# Arlinked-Can.net
KiCad netlist of a schematic drawn in EAGLE
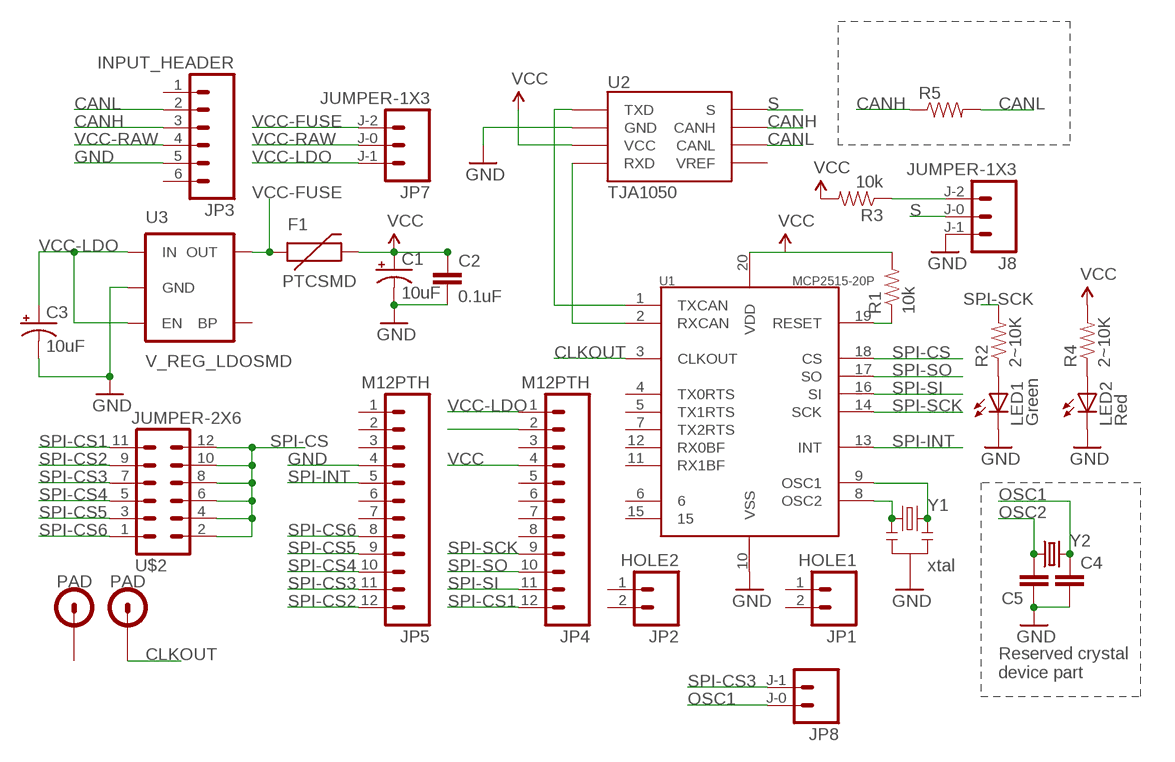
[diagram p0: schematic, sheet 1]

(export (version "E")
  (design (tool "Eeschema 10.0.6"))
  (components
    (comp (ref "C1")
      (value "10uF")
      (footprint "eagle-import:EIA3216")
      (libsource (lib "eagle-import") (part "CAP_POL1206"))
    )
    (comp (ref "C2")
      (value "0.1uF")
      (footprint "eagle-import:0402-CAP")
      (libsource (lib "eagle-import") (part "CAP0402-CAP"))
    )
    (comp (ref "C3")
      (value "10uF")
      (footprint "eagle-import:EIA3216")
      (libsource (lib "eagle-import") (part "CAP_POL1206"))
    )
    (comp (ref "C4")
      (value "CAP0402-CAP")
      (footprint "eagle-import:0402-CAP")
      (libsource (lib "eagle-import") (part "CAP0402-CAP"))
    )
    (comp (ref "C5")
      (value "CAP0402-CAP")
      (footprint "eagle-import:0402-CAP")
      (libsource (lib "eagle-import") (part "CAP0402-CAP"))
    )
    (comp (ref "F1")
      (value "PTCSMD")
      (footprint "eagle-import:PTC-1206")
      (libsource (lib "eagle-import") (part "PTCSMD"))
    )
    (comp (ref "J8")
      (value "JUMPER-1X3")
      (footprint "eagle-import:JUMPER-1X3-SMD-10")
      (libsource (lib "eagle-import") (part "JUMPER-1X3"))
    )
    (comp (ref "JP1")
      (value "HOLE1")
      (footprint "eagle-import:1X02")
      (libsource (lib "eagle-import") (part "M02PTH"))
    )
    (comp (ref "JP2")
      (value "HOLE2")
      (footprint "eagle-import:1X02")
      (libsource (lib "eagle-import") (part "M02PTH"))
    )
    (comp (ref "JP3")
      (value "INPUT_HEADER")
      (footprint "eagle-import:1X06")
      (libsource (lib "eagle-import") (part "M06SIP"))
    )
    (comp (ref "JP4")
      (value "M12PTH")
      (footprint "eagle-import:1X12")
      (libsource (lib "eagle-import") (part "M12PTH"))
    )
    (comp (ref "JP5")
      (value "M12PTH")
      (footprint "eagle-import:1X12")
      (libsource (lib "eagle-import") (part "M12PTH"))
    )
    (comp (ref "JP7")
      (value "JUMPER-1X3")
      (footprint "eagle-import:JUMPER-1X3-SMD-10")
      (libsource (lib "eagle-import") (part "JUMPER-1X3"))
    )
    (comp (ref "JP8")
      (value "JUMPER-1X2")
      (footprint "eagle-import:JUMPER-1X2-SMD-10")
      (libsource (lib "eagle-import") (part "JUMPER-1X2"))
    )
    (comp (ref "LED1")
      (value "Green")
      (footprint "eagle-import:LED-0603")
      (libsource (lib "eagle-import") (part "LED0603"))
    )
    (comp (ref "LED2")
      (value "Red")
      (footprint "eagle-import:LED-0603")
      (libsource (lib "eagle-import") (part "LED0603"))
    )
    (comp (ref "R1")
      (value "10k")
      (footprint "eagle-import:0603-RES")
      (libsource (lib "eagle-import") (part "RESISTOR0603-RES"))
    )
    (comp (ref "R2")
      (value "2~10K")
      (footprint "eagle-import:0402-RES")
      (libsource (lib "eagle-import") (part "RESISTOR0402-RES"))
    )
    (comp (ref "R3")
      (value "10k")
      (footprint "eagle-import:0603-RES")
      (libsource (lib "eagle-import") (part "RESISTOR0603-RES"))
    )
    (comp (ref "R4")
      (value "2~10K")
      (footprint "eagle-import:0402-RES")
      (libsource (lib "eagle-import") (part "RESISTOR0402-RES"))
    )
    (comp (ref "R5")
      (value "RESISTOR0603-RES")
      (footprint "eagle-import:0603-RES")
      (libsource (lib "eagle-import") (part "RESISTOR0603-RES"))
    )
    (comp (ref "U$1")
      (value "PAD")
      (footprint "eagle-import:PAD-HOLE-4MM")
      (libsource (lib "eagle-import") (part "PAD"))
    )
    (comp (ref "U$2")
      (value "JUMPER-2X6")
      (footprint "eagle-import:JUMPER-2X06-SMD")
      (libsource (lib "eagle-import") (part "JUMPER-2X6"))
    )
    (comp (ref "U$3")
      (value "PAD_SMD")
      (footprint "eagle-import:PAD-SMD-2MM")
      (libsource (lib "eagle-import") (part "PAD_SMD"))
    )
    (comp (ref "U1")
      (value "MCP2515-20P")
      (footprint "eagle-import:TSSOP20")
      (libsource (lib "eagle-import") (part "MCP2515-20P"))
    )
    (comp (ref "U2")
      (value "TJA1050")
      (footprint "eagle-import:SOIC-8")
      (libsource (lib "eagle-import") (part "TJA1050"))
    )
    (comp (ref "U3")
      (value "V_REG_LDOSMD")
      (footprint "eagle-import:SOT23-5")
      (libsource (lib "eagle-import") (part "V_REG_LDOSMD"))
    )
    (comp (ref "Y1")
      (value "xtal")
      (footprint "eagle-import:RESONATOR-SMD")
      (libsource (lib "eagle-import") (part "RESONATORSMD"))
    )
    (comp (ref "Y2")
      (value "CRYSTALPAD-ONLY")
      (footprint "eagle-import:HC49U-V")
      (libsource (lib "eagle-import") (part "CRYSTALPAD-ONLY"))
    )
  )
  (nets
    (net (code "1") (name "/CANH") (class "Default")
      (node (ref "JP3") (pin "3") (pinfunction "3_3") (pintype "passive"))
      (node (ref "R5") (pin "1") (pinfunction "1_1") (pintype "passive"))
      (node (ref "U2") (pin "7") (pinfunction "CANH_7") (pintype "bidirectional"))
    )
    (net (code "2") (name "/CANL") (class "Default")
      (node (ref "JP3") (pin "2") (pinfunction "2_2") (pintype "passive"))
      (node (ref "R5") (pin "2") (pinfunction "2_2") (pintype "passive"))
      (node (ref "U2") (pin "6") (pinfunction "CANL_6") (pintype "bidirectional"))
    )
    (net (code "3") (name "/CLKOUT") (class "Default")
      (node (ref "U$3") (pin "P$1") (pinfunction "P$1_P$1") (pintype "input"))
      (node (ref "U1") (pin "3") (pinfunction "CLKOUT_3") (pintype "bidirectional"))
    )
    (net (code "4") (name "/OSC1") (class "Default")
      (node (ref "C4") (pin "1") (pinfunction "1_1") (pintype "passive"))
      (node (ref "JP8") (pin "J-0") (pinfunction "J-1_J-0") (pintype "passive"))
      (node (ref "U1") (pin "9") (pinfunction "OSC1_9") (pintype "bidirectional"))
      (node (ref "Y1") (pin "3") (pinfunction "3_3") (pintype "passive"))
      (node (ref "Y2") (pin "2") (pinfunction "2_2") (pintype "passive"))
    )
    (net (code "5") (name "/OSC2") (class "Default")
      (node (ref "C5") (pin "2") (pinfunction "2_2") (pintype "passive"))
      (node (ref "U1") (pin "8") (pinfunction "OSC2_8") (pintype "bidirectional"))
      (node (ref "Y1") (pin "1") (pinfunction "1_1") (pintype "passive"))
      (node (ref "Y2") (pin "1") (pinfunction "1_1") (pintype "passive"))
    )
    (net (code "6") (name "/S") (class "Default")
      (node (ref "J8") (pin "J-0") (pinfunction "J-0_J-0") (pintype "passive"))
      (node (ref "U2") (pin "8") (pinfunction "S_8") (pintype "bidirectional"))
    )
    (net (code "7") (name "/SPI-CS") (class "Default")
      (node (ref "U$2") (pin "10") (pinfunction "10_10") (pintype "passive"))
      (node (ref "U$2") (pin "12") (pinfunction "12_12") (pintype "passive"))
      (node (ref "U$2") (pin "2") (pinfunction "2_2") (pintype "passive"))
      (node (ref "U$2") (pin "4") (pinfunction "4_4") (pintype "passive"))
      (node (ref "U$2") (pin "6") (pinfunction "6_6") (pintype "passive"))
      (node (ref "U$2") (pin "8") (pinfunction "8_8") (pintype "passive"))
      (node (ref "U1") (pin "18") (pinfunction "CS_18") (pintype "bidirectional"))
    )
    (net (code "8") (name "/SPI-CS1") (class "Default")
      (node (ref "JP4") (pin "12") (pinfunction "12_12") (pintype "passive"))
      (node (ref "U$2") (pin "11") (pinfunction "11_11") (pintype "passive"))
    )
    (net (code "9") (name "/SPI-CS2") (class "Default")
      (node (ref "JP5") (pin "12") (pinfunction "12_12") (pintype "passive"))
      (node (ref "U$2") (pin "9") (pinfunction "9_9") (pintype "passive"))
    )
    (net (code "10") (name "/SPI-CS3") (class "Default")
      (node (ref "JP5") (pin "11") (pinfunction "11_11") (pintype "passive"))
      (node (ref "JP8") (pin "J-1") (pinfunction "J-0_J-1") (pintype "passive"))
      (node (ref "U$2") (pin "7") (pinfunction "7_7") (pintype "passive"))
    )
    (net (code "11") (name "/SPI-CS4") (class "Default")
      (node (ref "JP5") (pin "10") (pinfunction "10_10") (pintype "passive"))
      (node (ref "U$2") (pin "5") (pinfunction "5_5") (pintype "passive"))
    )
    (net (code "12") (name "/SPI-CS5") (class "Default")
      (node (ref "JP5") (pin "9") (pinfunction "9_9") (pintype "passive"))
      (node (ref "U$2") (pin "3") (pinfunction "3_3") (pintype "passive"))
    )
    (net (code "13") (name "/SPI-CS6") (class "Default")
      (node (ref "JP5") (pin "8") (pinfunction "8_8") (pintype "passive"))
      (node (ref "U$2") (pin "1") (pinfunction "1_1") (pintype "passive"))
    )
    (net (code "14") (name "/SPI-INT") (class "Default")
      (node (ref "JP5") (pin "5") (pinfunction "5_5") (pintype "passive"))
      (node (ref "U1") (pin "13") (pinfunction "INT_13") (pintype "bidirectional"))
    )
    (net (code "15") (name "/SPI-SCK") (class "Default")
      (node (ref "JP4") (pin "9") (pinfunction "9_9") (pintype "passive"))
      (node (ref "R2") (pin "2") (pinfunction "2_2") (pintype "passive"))
      (node (ref "U1") (pin "14") (pinfunction "SCK_14") (pintype "bidirectional"))
    )
    (net (code "16") (name "/SPI-SI") (class "Default")
      (node (ref "JP4") (pin "11") (pinfunction "11_11") (pintype "passive"))
      (node (ref "U1") (pin "16") (pinfunction "SI_16") (pintype "bidirectional"))
    )
    (net (code "17") (name "/SPI-SO") (class "Default")
      (node (ref "JP4") (pin "10") (pinfunction "10_10") (pintype "passive"))
      (node (ref "U1") (pin "17") (pinfunction "SO_17") (pintype "bidirectional"))
    )
    (net (code "18") (name "/VCC-FUSE") (class "Default")
      (node (ref "F1") (pin "1") (pinfunction "1_1") (pintype "bidirectional"))
      (node (ref "JP7") (pin "J-2") (pinfunction "J-2_J-2") (pintype "passive"))
      (node (ref "U3") (pin "5") (pinfunction "OUT_5") (pintype "passive"))
    )
    (net (code "19") (name "/VCC-LDO") (class "Default")
      (node (ref "C3") (pin "A") (pinfunction "+_A") (pintype "passive"))
      (node (ref "JP4") (pin "1") (pinfunction "1_1") (pintype "passive"))
      (node (ref "JP7") (pin "J-1") (pinfunction "J-1_J-1") (pintype "passive"))
      (node (ref "U3") (pin "1") (pinfunction "IN_1") (pintype "input"))
      (node (ref "U3") (pin "3") (pinfunction "EN_3") (pintype "input"))
    )
    (net (code "20") (name "/VCC-RAW") (class "Default")
      (node (ref "JP3") (pin "4") (pinfunction "4_4") (pintype "passive"))
      (node (ref "JP7") (pin "J-0") (pinfunction "J-0_J-0") (pintype "passive"))
    )
    (net (code "21") (name "GND") (class "Default")
      (node (ref "C1") (pin "C") (pinfunction "-_C") (pintype "passive"))
      (node (ref "C2") (pin "2") (pinfunction "2_2") (pintype "passive"))
      (node (ref "C3") (pin "C") (pinfunction "-_C") (pintype "passive"))
      (node (ref "C4") (pin "2") (pinfunction "2_2") (pintype "passive"))
      (node (ref "C5") (pin "1") (pinfunction "1_1") (pintype "passive"))
      (node (ref "J8") (pin "J-1") (pinfunction "J-1_J-1") (pintype "passive"))
      (node (ref "JP3") (pin "5") (pinfunction "5_5") (pintype "passive"))
      (node (ref "JP4") (pin "2") (pinfunction "2_2") (pintype "passive"))
      (node (ref "JP5") (pin "4") (pinfunction "4_4") (pintype "passive"))
      (node (ref "LED1") (pin "C") (pinfunction "C_C") (pintype "passive"))
      (node (ref "LED2") (pin "C") (pinfunction "C_C") (pintype "passive"))
      (node (ref "U1") (pin "10") (pinfunction "VSS_10") (pintype "power_in"))
      (node (ref "U2") (pin "2") (pinfunction "GND_2") (pintype "bidirectional"))
      (node (ref "U3") (pin "2") (pinfunction "GND_2") (pintype "input"))
      (node (ref "Y1") (pin "2") (pinfunction "2_2") (pintype "passive"))
    )
    (net (code "22") (name "Net-(J8-PadJ-2)") (class "Default")
      (node (ref "J8") (pin "J-2") (pinfunction "J-2_J-2") (pintype "passive"))
      (node (ref "R3") (pin "1") (pinfunction "1_1") (pintype "passive"))
    )
    (net (code "23") (name "Net-(LED1-PadA)") (class "Default")
      (node (ref "LED1") (pin "A") (pinfunction "A_A") (pintype "passive"))
      (node (ref "R2") (pin "1") (pinfunction "1_1") (pintype "passive"))
    )
    (net (code "24") (name "Net-(LED2-PadA)") (class "Default")
      (node (ref "LED2") (pin "A") (pinfunction "A_A") (pintype "passive"))
      (node (ref "R4") (pin "1") (pinfunction "1_1") (pintype "passive"))
    )
    (net (code "25") (name "Net-(U1-RESET)") (class "Default")
      (node (ref "R1") (pin "1") (pinfunction "1_1") (pintype "passive"))
      (node (ref "U1") (pin "19") (pinfunction "RESET_19") (pintype "bidirectional"))
    )
    (net (code "26") (name "Net-(U1-RXCAN)") (class "Default")
      (node (ref "U1") (pin "2") (pinfunction "RXCAN_2") (pintype "bidirectional"))
      (node (ref "U2") (pin "4") (pinfunction "RXD_4") (pintype "bidirectional"))
    )
    (net (code "27") (name "Net-(U1-TXCAN)") (class "Default")
      (node (ref "U1") (pin "1") (pinfunction "TXCAN_1") (pintype "bidirectional"))
      (node (ref "U2") (pin "1") (pinfunction "TXD_1") (pintype "bidirectional"))
    )
    (net (code "28") (name "VCC") (class "Default")
      (node (ref "C1") (pin "A") (pinfunction "+_A") (pintype "passive"))
      (node (ref "C2") (pin "1") (pinfunction "1_1") (pintype "passive"))
      (node (ref "F1") (pin "2") (pinfunction "2_2") (pintype "bidirectional"))
      (node (ref "JP4") (pin "4") (pinfunction "4_4") (pintype "passive"))
      (node (ref "R1") (pin "2") (pinfunction "2_2") (pintype "passive"))
      (node (ref "R3") (pin "2") (pinfunction "2_2") (pintype "passive"))
      (node (ref "R4") (pin "2") (pinfunction "2_2") (pintype "passive"))
      (node (ref "U1") (pin "20") (pinfunction "VDD_20") (pintype "power_in"))
      (node (ref "U2") (pin "3") (pinfunction "VCC_3") (pintype "bidirectional"))
    )
    (net (code "29") (name "unconnected-(JP1-Pad1)") (class "Default")
      (node (ref "JP1") (pin "1") (pinfunction "1_1") (pintype "passive"))
    )
    (net (code "30") (name "unconnected-(JP1-Pad2)") (class "Default")
      (node (ref "JP1") (pin "2") (pinfunction "2_2") (pintype "passive"))
    )
    (net (code "31") (name "unconnected-(JP2-Pad1)") (class "Default")
      (node (ref "JP2") (pin "1") (pinfunction "1_1") (pintype "passive"))
    )
    (net (code "32") (name "unconnected-(JP2-Pad2)") (class "Default")
      (node (ref "JP2") (pin "2") (pinfunction "2_2") (pintype "passive"))
    )
    (net (code "33") (name "unconnected-(JP3-Pad1)") (class "Default")
      (node (ref "JP3") (pin "1") (pinfunction "1_1") (pintype "passive"))
    )
    (net (code "34") (name "unconnected-(JP3-Pad6)") (class "Default")
      (node (ref "JP3") (pin "6") (pinfunction "6_6") (pintype "passive"))
    )
    (net (code "35") (name "unconnected-(JP4-Pad3)") (class "Default")
      (node (ref "JP4") (pin "3") (pinfunction "3_3") (pintype "passive"))
    )
    (net (code "36") (name "unconnected-(JP4-Pad5)") (class "Default")
      (node (ref "JP4") (pin "5") (pinfunction "5_5") (pintype "passive"))
    )
    (net (code "37") (name "unconnected-(JP4-Pad6)") (class "Default")
      (node (ref "JP4") (pin "6") (pinfunction "6_6") (pintype "passive"))
    )
    (net (code "38") (name "unconnected-(JP4-Pad7)") (class "Default")
      (node (ref "JP4") (pin "7") (pinfunction "7_7") (pintype "passive"))
    )
    (net (code "39") (name "unconnected-(JP4-Pad8)") (class "Default")
      (node (ref "JP4") (pin "8") (pinfunction "8_8") (pintype "passive"))
    )
    (net (code "40") (name "unconnected-(JP5-Pad1)") (class "Default")
      (node (ref "JP5") (pin "1") (pinfunction "1_1") (pintype "passive"))
    )
    (net (code "41") (name "unconnected-(JP5-Pad2)") (class "Default")
      (node (ref "JP5") (pin "2") (pinfunction "2_2") (pintype "passive"))
    )
    (net (code "42") (name "unconnected-(JP5-Pad3)") (class "Default")
      (node (ref "JP5") (pin "3") (pinfunction "3_3") (pintype "passive"))
    )
    (net (code "43") (name "unconnected-(JP5-Pad6)") (class "Default")
      (node (ref "JP5") (pin "6") (pinfunction "6_6") (pintype "passive"))
    )
    (net (code "44") (name "unconnected-(JP5-Pad7)") (class "Default")
      (node (ref "JP5") (pin "7") (pinfunction "7_7") (pintype "passive"))
    )
    (net (code "45") (name "unconnected-(U$1-PadP$1)") (class "Default")
      (node (ref "U$1") (pin "P$1") (pinfunction "P$1_P$1") (pintype "input"))
    )
    (net (code "46") (name "unconnected-(U1-Pad6)") (class "Default")
      (node (ref "U1") (pin "6") (pinfunction "6_6") (pintype "no_connect"))
    )
    (net (code "47") (name "unconnected-(U1-Pad15)") (class "Default")
      (node (ref "U1") (pin "15") (pinfunction "15_15") (pintype "no_connect"))
    )
    (net (code "48") (name "unconnected-(U1-RX0BF-Pad12)") (class "Default")
      (node (ref "U1") (pin "12") (pinfunction "RX0BF_12") (pintype "bidirectional"))
    )
    (net (code "49") (name "unconnected-(U1-RX1BF-Pad11)") (class "Default")
      (node (ref "U1") (pin "11") (pinfunction "RX1BF_11") (pintype "bidirectional"))
    )
    (net (code "50") (name "unconnected-(U1-TX0RTS-Pad4)") (class "Default")
      (node (ref "U1") (pin "4") (pinfunction "TX0RTS_4") (pintype "bidirectional"))
    )
    (net (code "51") (name "unconnected-(U1-TX1RTS-Pad5)") (class "Default")
      (node (ref "U1") (pin "5") (pinfunction "TX1RTS_5") (pintype "bidirectional"))
    )
    (net (code "52") (name "unconnected-(U1-TX2RTS-Pad7)") (class "Default")
      (node (ref "U1") (pin "7") (pinfunction "TX2RTS_7") (pintype "bidirectional"))
    )
    (net (code "53") (name "unconnected-(U2-VREF-Pad5)") (class "Default")
      (node (ref "U2") (pin "5") (pinfunction "VREF_5") (pintype "bidirectional"))
    )
    (net (code "54") (name "unconnected-(U3-BP-Pad4)") (class "Default")
      (node (ref "U3") (pin "4") (pinfunction "BP_4") (pintype "input"))
    )
  )
)
